# latch_THT_XOR.net
KiCad netlist of a schematic drawn in EAGLE
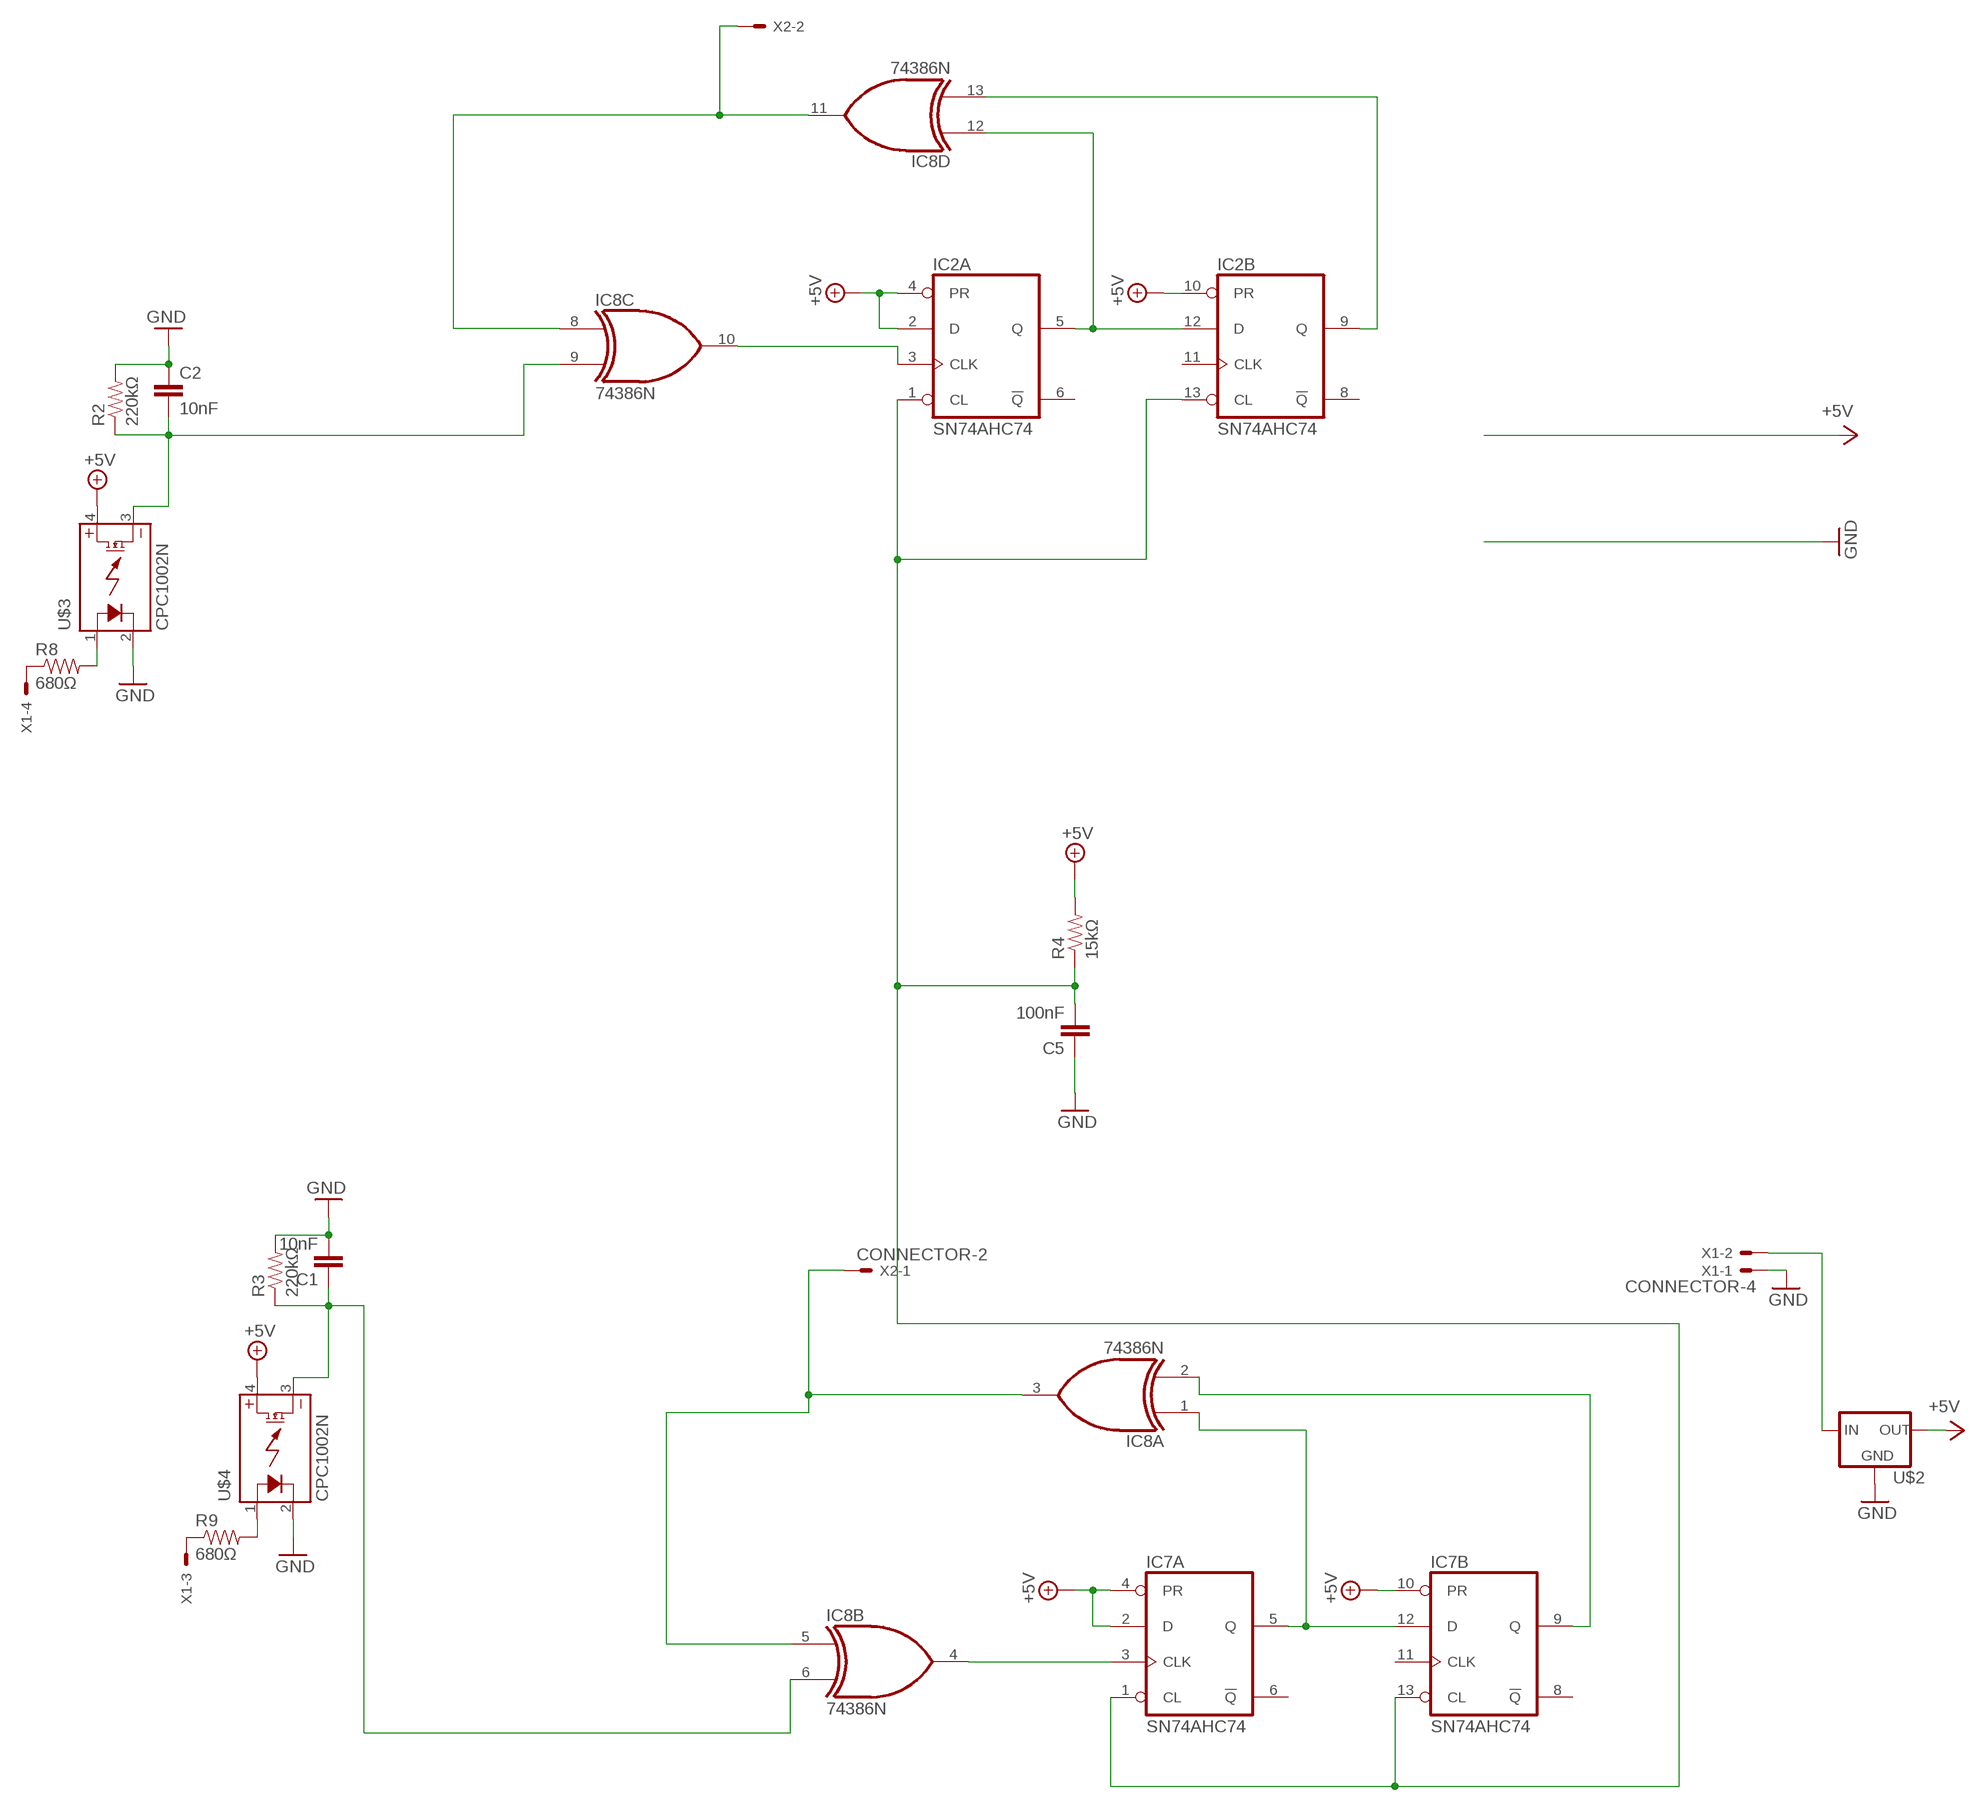
[diagram p0: schematic, sheet 1]

(export (version "E")
  (design (tool "Eeschema 10.0.6"))
  (components
    (comp (ref "C1")
      (value "10nF")
      (footprint "eagle-import:AXIAL-5MM")
      (libsource (lib "eagle-import") (part "CAP_"))
    )
    (comp (ref "C2")
      (value "10nF")
      (footprint "eagle-import:AXIAL-5MM")
      (libsource (lib "eagle-import") (part "CAP_"))
    )
    (comp (ref "C5")
      (value "100nF")
      (footprint "eagle-import:AXIAL-5MM")
      (libsource (lib "eagle-import") (part "CAP_"))
    )
    (comp (ref "IC2")
      (value "SN74AHC74")
      (footprint "eagle-import:DIL14")
      (libsource (lib "eagle-import") (part "SN74AHC74"))
    )
    (comp (ref "IC7")
      (value "SN74AHC74")
      (footprint "eagle-import:DIL14")
      (libsource (lib "eagle-import") (part "SN74AHC74"))
    )
    (comp (ref "IC8")
      (value "74386N")
      (footprint "eagle-import:DIL14")
      (libsource (lib "eagle-import") (part "74386N"))
    )
    (comp (ref "R2")
      (value "220kΩ")
      (footprint "eagle-import:AXIAL-0.4")
      (libsource (lib "eagle-import") (part "RESISTORPTH-1/4W"))
    )
    (comp (ref "R3")
      (value "220kΩ")
      (footprint "eagle-import:AXIAL-0.4")
      (libsource (lib "eagle-import") (part "RESISTORPTH-1/4W"))
    )
    (comp (ref "R4")
      (value "15kΩ")
      (footprint "eagle-import:AXIAL-0.4")
      (libsource (lib "eagle-import") (part "RESISTORPTH-1/4W"))
    )
    (comp (ref "R8")
      (value "680Ω")
      (footprint "eagle-import:AXIAL-0.4")
      (libsource (lib "eagle-import") (part "RESISTORPTH-1/4W"))
    )
    (comp (ref "R9")
      (value "680Ω")
      (footprint "eagle-import:AXIAL-0.4")
      (libsource (lib "eagle-import") (part "RESISTORPTH-1/4W"))
    )
    (comp (ref "U$2")
      (value "5VREG_LM340-NLM340T-5.0/NOPB")
      (footprint "eagle-import:TO-220")
      (libsource (lib "eagle-import") (part "5VREG_LM340-NLM340T-5.0/NOPB"))
    )
    (comp (ref "U$3")
      (value "CPC1002N")
      (footprint "eagle-import:SOP04")
      (libsource (lib "eagle-import") (part "CPC1002N"))
    )
    (comp (ref "U$4")
      (value "CPC1002N")
      (footprint "eagle-import:SOP04")
      (libsource (lib "eagle-import") (part "CPC1002N"))
    )
    (comp (ref "X1")
      (value "CONNECTOR-4")
      (footprint "eagle-import:MINIFIT_5566-4")
      (libsource (lib "eagle-import") (part "CONNECTOR-4"))
    )
    (comp (ref "X2")
      (value "CONNECTOR-2")
      (footprint "eagle-import:MINIFIT_5566-2")
      (libsource (lib "eagle-import") (part "CONNECTOR-2"))
    )
  )
  (nets
    (net (code "1") (name "+5V") (class "Default")
      (node (ref "IC2") (pin "10") (pinfunction "PR_10") (pintype "input"))
      (node (ref "IC2") (pin "2") (pinfunction "D_2") (pintype "input"))
      (node (ref "IC2") (pin "4") (pinfunction "PR_4") (pintype "input"))
      (node (ref "IC7") (pin "10") (pinfunction "PR_10") (pintype "input"))
      (node (ref "IC7") (pin "2") (pinfunction "D_2") (pintype "input"))
      (node (ref "IC7") (pin "4") (pinfunction "PR_4") (pintype "input"))
      (node (ref "R4") (pin "P$2") (pinfunction "2_P$2") (pintype "passive"))
      (node (ref "U$2") (pin "3") (pinfunction "OUT_3") (pintype "output"))
      (node (ref "U$3") (pin "4") (pinfunction "DC+_4") (pintype "passive"))
      (node (ref "U$4") (pin "4") (pinfunction "DC+_4") (pintype "passive"))
    )
    (net (code "2") (name "GND") (class "Default")
      (node (ref "C1") (pin "P$2") (pinfunction "2_P$2") (pintype "passive"))
      (node (ref "C2") (pin "P$1") (pinfunction "1_P$1") (pintype "passive"))
      (node (ref "C5") (pin "P$1") (pinfunction "1_P$1") (pintype "passive"))
      (node (ref "R2") (pin "P$2") (pinfunction "2_P$2") (pintype "passive"))
      (node (ref "R3") (pin "P$2") (pinfunction "2_P$2") (pintype "passive"))
      (node (ref "U$2") (pin "2") (pinfunction "GND_2") (pintype "input"))
      (node (ref "U$3") (pin "2") (pinfunction "CONTROL-_2") (pintype "passive"))
      (node (ref "U$4") (pin "2") (pinfunction "CONTROL-_2") (pintype "passive"))
      (node (ref "X1") (pin "1") (pinfunction "S_1") (pintype "passive"))
    )
    (net (code "3") (name "Net-(C1-1)") (class "Default")
      (node (ref "C1") (pin "P$1") (pinfunction "1_P$1") (pintype "passive"))
      (node (ref "IC8") (pin "6") (pinfunction "I1_6") (pintype "input"))
      (node (ref "R3") (pin "P$1") (pinfunction "1_P$1") (pintype "passive"))
      (node (ref "U$4") (pin "3") (pinfunction "DC-_3") (pintype "passive"))
    )
    (net (code "4") (name "Net-(C2-2)") (class "Default")
      (node (ref "C2") (pin "P$2") (pinfunction "2_P$2") (pintype "passive"))
      (node (ref "IC8") (pin "9") (pinfunction "I1_9") (pintype "input"))
      (node (ref "R2") (pin "P$1") (pinfunction "1_P$1") (pintype "passive"))
      (node (ref "U$3") (pin "3") (pinfunction "DC-_3") (pintype "passive"))
    )
    (net (code "5") (name "Net-(C5-2)") (class "Default")
      (node (ref "C5") (pin "P$2") (pinfunction "2_P$2") (pintype "passive"))
      (node (ref "IC2") (pin "1") (pinfunction "CL_1") (pintype "input"))
      (node (ref "IC2") (pin "13") (pinfunction "CL_13") (pintype "input"))
      (node (ref "IC7") (pin "1") (pinfunction "CL_1") (pintype "input"))
      (node (ref "IC7") (pin "13") (pinfunction "CL_13") (pintype "input"))
      (node (ref "R4") (pin "P$1") (pinfunction "1_P$1") (pintype "passive"))
    )
    (net (code "6") (name "Net-(IC2A-CLK)") (class "Default")
      (node (ref "IC2") (pin "3") (pinfunction "CLK_3") (pintype "input"))
      (node (ref "IC8") (pin "10") (pinfunction "O_10") (pintype "output"))
    )
    (net (code "7") (name "Net-(IC2A-Q)") (class "Default")
      (node (ref "IC2") (pin "12") (pinfunction "D_12") (pintype "input"))
      (node (ref "IC2") (pin "5") (pinfunction "Q_5") (pintype "output"))
      (node (ref "IC8") (pin "12") (pinfunction "I0_12") (pintype "input"))
    )
    (net (code "8") (name "Net-(IC2B-Q)") (class "Default")
      (node (ref "IC2") (pin "9") (pinfunction "Q_9") (pintype "output"))
      (node (ref "IC8") (pin "13") (pinfunction "I1_13") (pintype "input"))
    )
    (net (code "9") (name "Net-(IC7A-CLK)") (class "Default")
      (node (ref "IC7") (pin "3") (pinfunction "CLK_3") (pintype "input"))
      (node (ref "IC8") (pin "4") (pinfunction "O_4") (pintype "output"))
    )
    (net (code "10") (name "Net-(IC7A-Q)") (class "Default")
      (node (ref "IC7") (pin "12") (pinfunction "D_12") (pintype "input"))
      (node (ref "IC7") (pin "5") (pinfunction "Q_5") (pintype "output"))
      (node (ref "IC8") (pin "1") (pinfunction "I0_1") (pintype "input"))
    )
    (net (code "11") (name "Net-(IC7B-Q)") (class "Default")
      (node (ref "IC7") (pin "9") (pinfunction "Q_9") (pintype "output"))
      (node (ref "IC8") (pin "2") (pinfunction "I1_2") (pintype "input"))
    )
    (net (code "12") (name "Net-(IC8A-O)") (class "Default")
      (node (ref "IC8") (pin "3") (pinfunction "O_3") (pintype "output"))
      (node (ref "IC8") (pin "5") (pinfunction "I0_5") (pintype "input"))
      (node (ref "X2") (pin "1") (pinfunction "S_1") (pintype "passive"))
    )
    (net (code "13") (name "Net-(IC8C-I0)") (class "Default")
      (node (ref "IC8") (pin "11") (pinfunction "O_11") (pintype "output"))
      (node (ref "IC8") (pin "8") (pinfunction "I0_8") (pintype "input"))
      (node (ref "X2") (pin "2") (pinfunction "S_2") (pintype "passive"))
    )
    (net (code "14") (name "Net-(R8-1)") (class "Default")
      (node (ref "R8") (pin "P$1") (pinfunction "1_P$1") (pintype "passive"))
      (node (ref "X1") (pin "4") (pinfunction "S_4") (pintype "passive"))
    )
    (net (code "15") (name "Net-(R8-2)") (class "Default")
      (node (ref "R8") (pin "P$2") (pinfunction "2_P$2") (pintype "passive"))
      (node (ref "U$3") (pin "1") (pinfunction "CONTROL+_1") (pintype "passive"))
    )
    (net (code "16") (name "Net-(R9-1)") (class "Default")
      (node (ref "R9") (pin "P$1") (pinfunction "1_P$1") (pintype "passive"))
      (node (ref "X1") (pin "3") (pinfunction "S_3") (pintype "passive"))
    )
    (net (code "17") (name "Net-(R9-2)") (class "Default")
      (node (ref "R9") (pin "P$2") (pinfunction "2_P$2") (pintype "passive"))
      (node (ref "U$4") (pin "1") (pinfunction "CONTROL+_1") (pintype "passive"))
    )
    (net (code "18") (name "Net-(U$2-IN)") (class "Default")
      (node (ref "U$2") (pin "1") (pinfunction "IN_1") (pintype "input"))
      (node (ref "X1") (pin "2") (pinfunction "S_2") (pintype "passive"))
    )
    (net (code "19") (name "unconnected-(IC2A-~{Q}-Pad6)") (class "Default")
      (node (ref "IC2") (pin "6") (pinfunction "~{Q}_6") (pintype "output"))
    )
    (net (code "20") (name "unconnected-(IC2B-CLK-Pad11)") (class "Default")
      (node (ref "IC2") (pin "11") (pinfunction "CLK_11") (pintype "input"))
    )
    (net (code "21") (name "unconnected-(IC2B-~{Q}-Pad8)") (class "Default")
      (node (ref "IC2") (pin "8") (pinfunction "~{Q}_8") (pintype "output"))
    )
    (net (code "22") (name "unconnected-(IC7A-~{Q}-Pad6)") (class "Default")
      (node (ref "IC7") (pin "6") (pinfunction "~{Q}_6") (pintype "output"))
    )
    (net (code "23") (name "unconnected-(IC7B-CLK-Pad11)") (class "Default")
      (node (ref "IC7") (pin "11") (pinfunction "CLK_11") (pintype "input"))
    )
    (net (code "24") (name "unconnected-(IC7B-~{Q}-Pad8)") (class "Default")
      (node (ref "IC7") (pin "8") (pinfunction "~{Q}_8") (pintype "output"))
    )
  )
)
